# onion_dip_v1.net
KiCad netlist of a schematic drawn in EAGLE
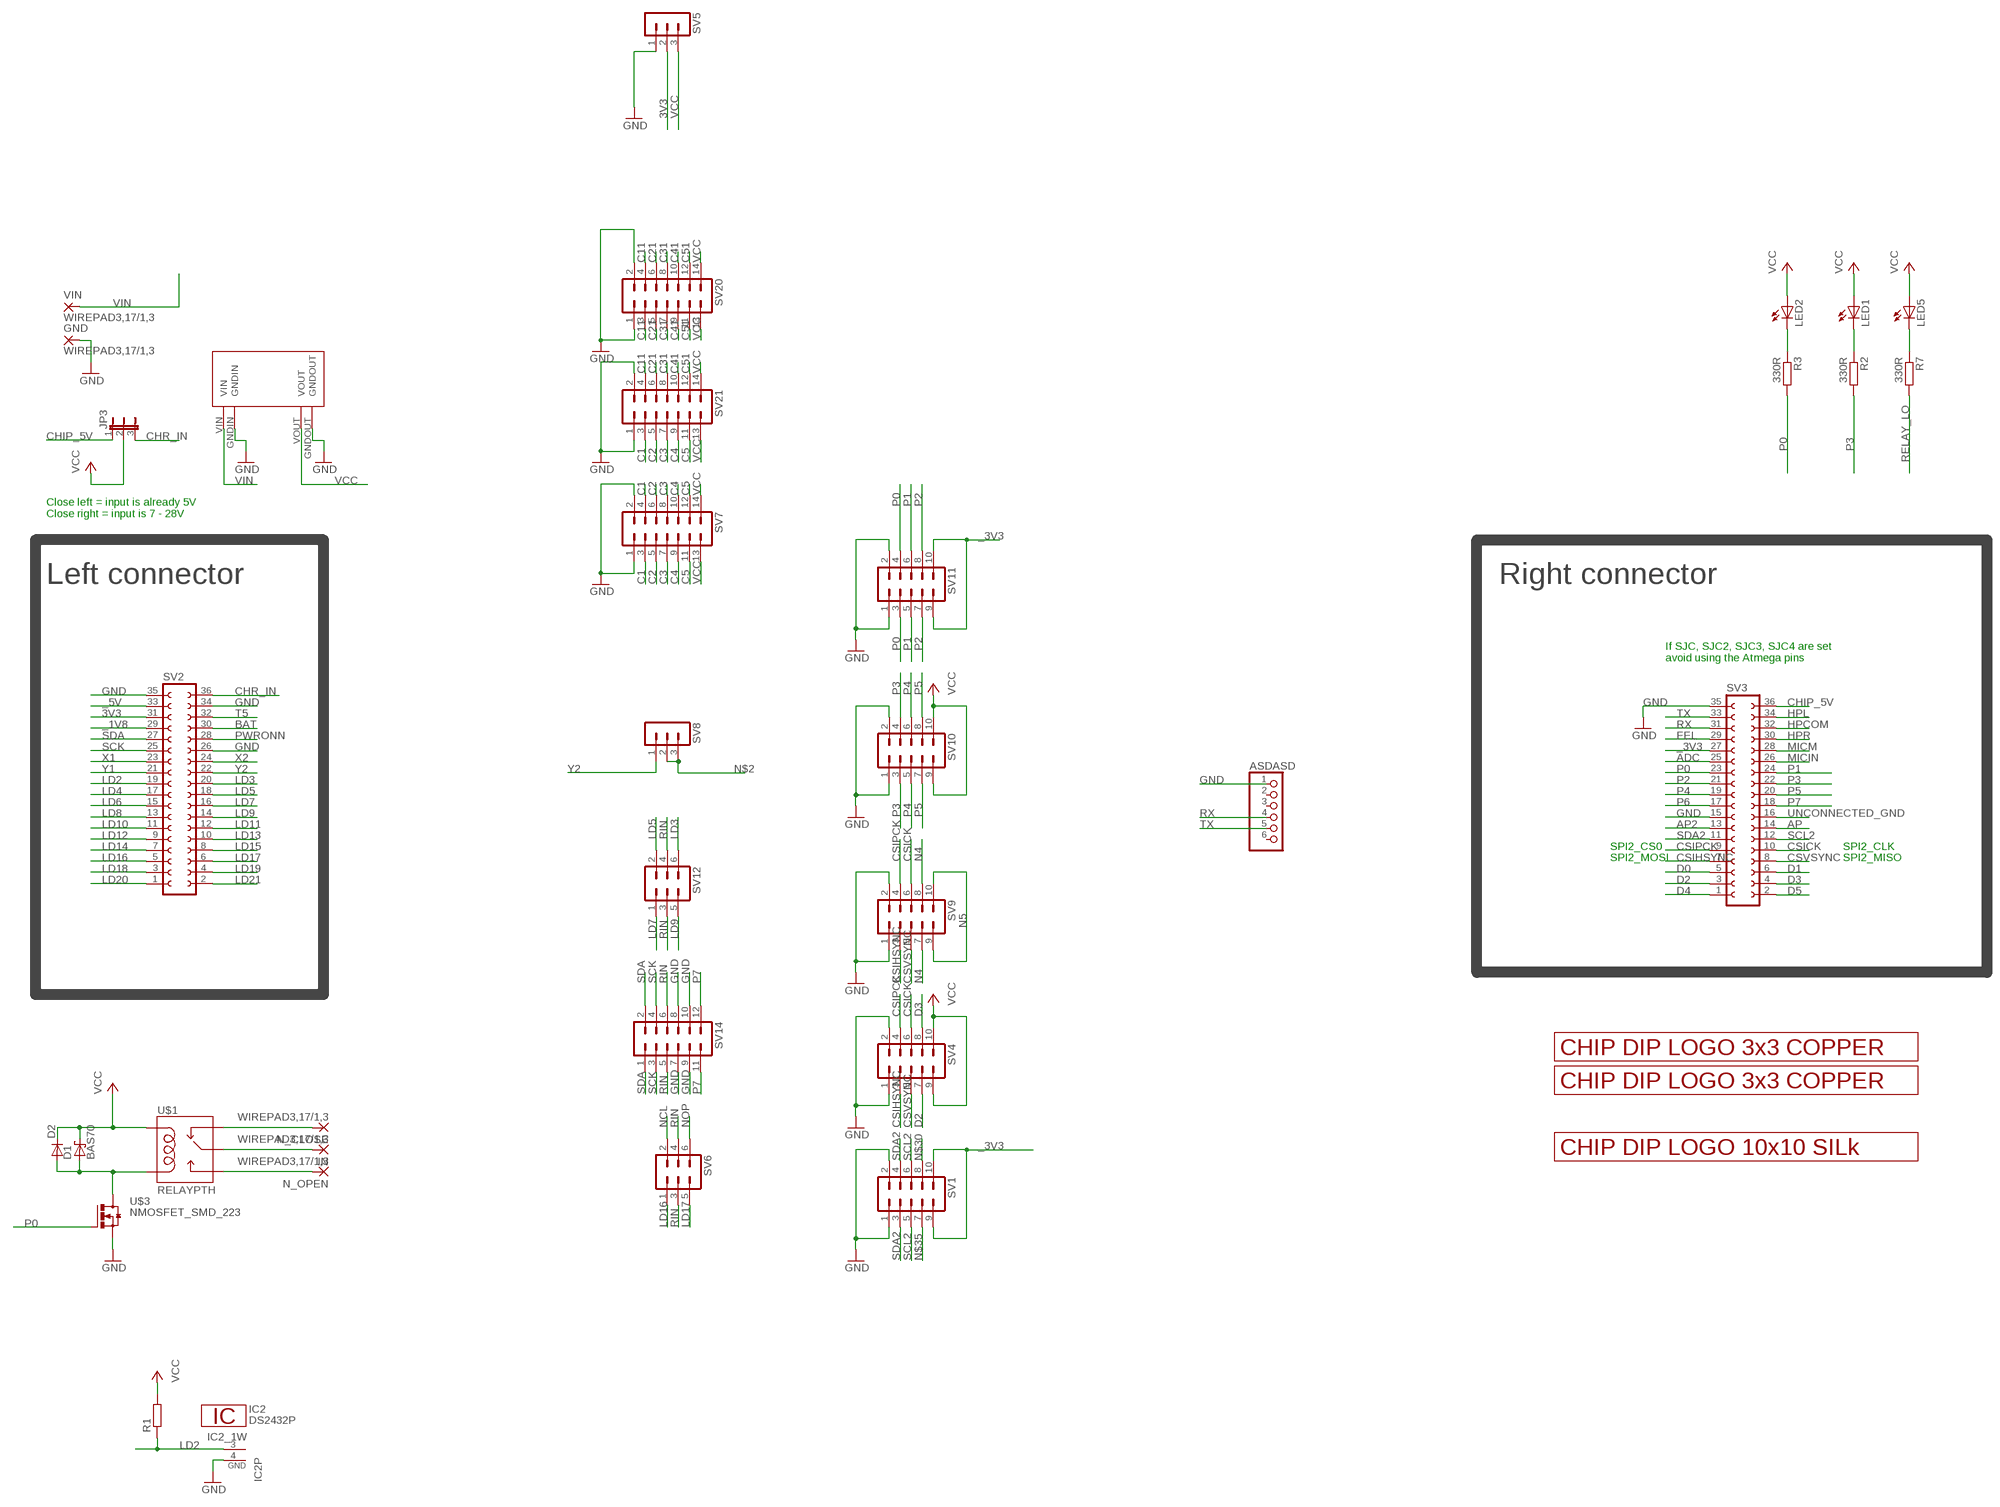
[diagram p0: schematic, sheet 1]

(export (version "E")
  (design (tool "Eeschema 10.0.6"))
  (components
    (comp (ref "ASDASD")
      (value "PINHD-1X6")
      (footprint "eagle-import:1X06")
      (libsource (lib "eagle-import") (part "PINHD-1X6"))
    )
    (comp (ref "D1")
      (value "BAS70")
      (footprint "eagle-import:SOT23")
      (libsource (lib "eagle-import") (part "BAS70"))
    )
    (comp (ref "D2")
      (value "DIODE-SMB")
      (footprint "eagle-import:SMB")
      (libsource (lib "eagle-import") (part "DIODE-SMB"))
    )
    (comp (ref "GND")
      (value "WIREPAD3,17/1,3")
      (footprint "eagle-import:3,17_1,3")
      (libsource (lib "eagle-import") (part "WIREPAD3,17/1,3"))
    )
    (comp (ref "IC2")
      (value "DS2432P")
      (footprint "eagle-import:TSOC6")
      (libsource (lib "eagle-import") (part "DS2432P"))
    )
    (comp (ref "IN")
      (value "WIREPAD3,17/1,3")
      (footprint "eagle-import:3,17_1,3")
      (libsource (lib "eagle-import") (part "WIREPAD3,17/1,3"))
    )
    (comp (ref "JP3")
      (value "JP2E")
      (footprint "eagle-import:JP2")
      (libsource (lib "eagle-import") (part "JP2E"))
    )
    (comp (ref "LED1")
      (value "LEDCHIP-LED0805")
      (footprint "eagle-import:CHIP-LED0805")
      (libsource (lib "eagle-import") (part "LEDCHIP-LED0805"))
    )
    (comp (ref "LED2")
      (value "LEDCHIP-LED0805")
      (footprint "eagle-import:CHIP-LED0805")
      (libsource (lib "eagle-import") (part "LEDCHIP-LED0805"))
    )
    (comp (ref "LED5")
      (value "LEDCHIP-LED0805")
      (footprint "eagle-import:CHIP-LED0805")
      (libsource (lib "eagle-import") (part "LEDCHIP-LED0805"))
    )
    (comp (ref "N_CLOSE")
      (value "WIREPAD3,17/1,3")
      (footprint "eagle-import:3,17_1,3")
      (libsource (lib "eagle-import") (part "WIREPAD3,17/1,3"))
    )
    (comp (ref "N_OPEN")
      (value "WIREPAD3,17/1,3")
      (footprint "eagle-import:3,17_1,3")
      (libsource (lib "eagle-import") (part "WIREPAD3,17/1,3"))
    )
    (comp (ref "R1")
      (value "R-EU_R0805")
      (footprint "eagle-import:R0805")
      (libsource (lib "eagle-import") (part "R-EU_R0805"))
    )
    (comp (ref "R2")
      (value "330R")
      (footprint "eagle-import:R0805")
      (libsource (lib "eagle-import") (part "R-EU_R0805"))
    )
    (comp (ref "R3")
      (value "330R")
      (footprint "eagle-import:R0805")
      (libsource (lib "eagle-import") (part "R-EU_R0805"))
    )
    (comp (ref "R7")
      (value "330R")
      (footprint "eagle-import:R0805")
      (libsource (lib "eagle-import") (part "R-EU_R0805"))
    )
    (comp (ref "SV1")
      (value "MA05-2")
      (footprint "eagle-import:MA05-2")
      (libsource (lib "eagle-import") (part "MA05-2"))
    )
    (comp (ref "SV2")
      (value "FE18-2")
      (footprint "eagle-import:FE18-2")
      (libsource (lib "eagle-import") (part "FE18-2"))
    )
    (comp (ref "SV3")
      (value "FE18-2")
      (footprint "eagle-import:FE18-2")
      (libsource (lib "eagle-import") (part "FE18-2"))
    )
    (comp (ref "SV4")
      (value "MA05-2")
      (footprint "eagle-import:MA05-2")
      (libsource (lib "eagle-import") (part "MA05-2"))
    )
    (comp (ref "SV5")
      (value "MA03-1")
      (footprint "eagle-import:MA03-1")
      (libsource (lib "eagle-import") (part "MA03-1"))
    )
    (comp (ref "SV6")
      (value "MA03-2")
      (footprint "eagle-import:MA03-2")
      (libsource (lib "eagle-import") (part "MA03-2"))
    )
    (comp (ref "SV7")
      (value "MA07-2")
      (footprint "eagle-import:MA07-2")
      (libsource (lib "eagle-import") (part "MA07-2"))
    )
    (comp (ref "SV8")
      (value "MA03-1")
      (footprint "eagle-import:MA03-1")
      (libsource (lib "eagle-import") (part "MA03-1"))
    )
    (comp (ref "SV9")
      (value "MA05-2")
      (footprint "eagle-import:MA05-2")
      (libsource (lib "eagle-import") (part "MA05-2"))
    )
    (comp (ref "SV10")
      (value "MA05-2")
      (footprint "eagle-import:MA05-2")
      (libsource (lib "eagle-import") (part "MA05-2"))
    )
    (comp (ref "SV11")
      (value "MA05-2")
      (footprint "eagle-import:MA05-2")
      (libsource (lib "eagle-import") (part "MA05-2"))
    )
    (comp (ref "SV12")
      (value "MA03-2")
      (footprint "eagle-import:MA03-2")
      (libsource (lib "eagle-import") (part "MA03-2"))
    )
    (comp (ref "SV14")
      (value "MA06-2")
      (footprint "eagle-import:MA06-2")
      (libsource (lib "eagle-import") (part "MA06-2"))
    )
    (comp (ref "SV20")
      (value "MA07-2")
      (footprint "eagle-import:MA07-2")
      (libsource (lib "eagle-import") (part "MA07-2"))
    )
    (comp (ref "SV21")
      (value "MA07-2")
      (footprint "eagle-import:MA07-2")
      (libsource (lib "eagle-import") (part "MA07-2"))
    )
    (comp (ref "U$1")
      (value "RELAYPTH")
      (footprint "eagle-import:SRD-05VDC-SL-C")
      (libsource (lib "eagle-import") (part "RELAYPTH"))
    )
    (comp (ref "U$3")
      (value "NMOSFET_SMD_223")
      (footprint "eagle-import:SOT223")
      (libsource (lib "eagle-import") (part "NMOSFET_SMD_223"))
    )
    (comp (ref "U$4")
      (value "LOGO_3X3_COPPER")
      (footprint "eagle-import:LOGO_3X3_COPPER")
      (libsource (lib "eagle-import") (part "LOGO_3X3_COPPER"))
    )
    (comp (ref "U$5")
      (value "LOGO_10X10_SILK")
      (footprint "eagle-import:LOGO_10X10_SILK")
      (libsource (lib "eagle-import") (part "LOGO_10X10_SILK"))
    )
    (comp (ref "U$6")
      (value "LOGO_3X3_COPPER")
      (footprint "eagle-import:LOGO_3X3_COPPER")
      (libsource (lib "eagle-import") (part "LOGO_3X3_COPPER"))
    )
    (comp (ref "U$9")
      (value "MP1584EN_FRAMELESS")
      (footprint "eagle-import:MP1584EN_FRAMELESS")
      (libsource (lib "eagle-import") (part "MP1584EN_FRAMELESS"))
    )
    (comp (ref "VIN")
      (value "WIREPAD3,17/1,3")
      (footprint "eagle-import:3,17_1,3")
      (libsource (lib "eagle-import") (part "WIREPAD3,17/1,3"))
    )
  )
  (nets
    (net (code "1") (name "/3V3") (class "Default")
      (node (ref "SV2") (pin "31") (pinfunction "31_31") (pintype "passive"))
      (node (ref "SV5") (pin "2") (pinfunction "2_2") (pintype "passive"))
    )
    (net (code "2") (name "/ADC") (class "Default")
      (node (ref "SV3") (pin "25") (pinfunction "25_25") (pintype "passive"))
    )
    (net (code "3") (name "/AP") (class "Default")
      (node (ref "SV3") (pin "14") (pinfunction "14_14") (pintype "passive"))
    )
    (net (code "4") (name "/AP2") (class "Default")
      (node (ref "SV3") (pin "13") (pinfunction "13_13") (pintype "passive"))
    )
    (net (code "5") (name "/BAT") (class "Default")
      (node (ref "SV2") (pin "30") (pinfunction "30_30") (pintype "passive"))
    )
    (net (code "6") (name "/C1") (class "Default")
      (node (ref "SV21") (pin "3") (pinfunction "3_3") (pintype "passive"))
      (node (ref "SV7") (pin "3") (pinfunction "3_3") (pintype "passive"))
      (node (ref "SV7") (pin "4") (pinfunction "4_4") (pintype "passive"))
    )
    (net (code "7") (name "/C2") (class "Default")
      (node (ref "SV21") (pin "5") (pinfunction "5_5") (pintype "passive"))
      (node (ref "SV7") (pin "5") (pinfunction "5_5") (pintype "passive"))
      (node (ref "SV7") (pin "6") (pinfunction "6_6") (pintype "passive"))
    )
    (net (code "8") (name "/C3") (class "Default")
      (node (ref "SV21") (pin "7") (pinfunction "7_7") (pintype "passive"))
      (node (ref "SV7") (pin "7") (pinfunction "7_7") (pintype "passive"))
      (node (ref "SV7") (pin "8") (pinfunction "8_8") (pintype "passive"))
    )
    (net (code "9") (name "/C4") (class "Default")
      (node (ref "SV21") (pin "9") (pinfunction "9_9") (pintype "passive"))
      (node (ref "SV7") (pin "10") (pinfunction "10_10") (pintype "passive"))
      (node (ref "SV7") (pin "9") (pinfunction "9_9") (pintype "passive"))
    )
    (net (code "10") (name "/C5") (class "Default")
      (node (ref "SV21") (pin "11") (pinfunction "11_11") (pintype "passive"))
      (node (ref "SV7") (pin "11") (pinfunction "11_11") (pintype "passive"))
      (node (ref "SV7") (pin "12") (pinfunction "12_12") (pintype "passive"))
    )
    (net (code "11") (name "/C11") (class "Default")
      (node (ref "SV20") (pin "3") (pinfunction "3_3") (pintype "passive"))
      (node (ref "SV20") (pin "4") (pinfunction "4_4") (pintype "passive"))
      (node (ref "SV21") (pin "4") (pinfunction "4_4") (pintype "passive"))
    )
    (net (code "12") (name "/C21") (class "Default")
      (node (ref "SV20") (pin "5") (pinfunction "5_5") (pintype "passive"))
      (node (ref "SV20") (pin "6") (pinfunction "6_6") (pintype "passive"))
      (node (ref "SV21") (pin "6") (pinfunction "6_6") (pintype "passive"))
    )
    (net (code "13") (name "/C31") (class "Default")
      (node (ref "SV20") (pin "7") (pinfunction "7_7") (pintype "passive"))
      (node (ref "SV20") (pin "8") (pinfunction "8_8") (pintype "passive"))
      (node (ref "SV21") (pin "8") (pinfunction "8_8") (pintype "passive"))
    )
    (net (code "14") (name "/C41") (class "Default")
      (node (ref "SV20") (pin "10") (pinfunction "10_10") (pintype "passive"))
      (node (ref "SV20") (pin "9") (pinfunction "9_9") (pintype "passive"))
      (node (ref "SV21") (pin "10") (pinfunction "10_10") (pintype "passive"))
    )
    (net (code "15") (name "/C51") (class "Default")
      (node (ref "SV20") (pin "11") (pinfunction "11_11") (pintype "passive"))
      (node (ref "SV20") (pin "12") (pinfunction "12_12") (pintype "passive"))
      (node (ref "SV21") (pin "12") (pinfunction "12_12") (pintype "passive"))
    )
    (net (code "16") (name "/CHIP_5V") (class "Default")
      (node (ref "JP3") (pin "1") (pinfunction "1_1") (pintype "passive"))
      (node (ref "SV3") (pin "36") (pinfunction "36_36") (pintype "passive"))
    )
    (net (code "17") (name "/CHR_IN") (class "Default")
      (node (ref "JP3") (pin "3") (pinfunction "3_3") (pintype "passive"))
      (node (ref "SV2") (pin "36") (pinfunction "36_36") (pintype "passive"))
    )
    (net (code "18") (name "/CSICK") (class "Default")
      (node (ref "SV3") (pin "10") (pinfunction "10_10") (pintype "passive"))
      (node (ref "SV4") (pin "6") (pinfunction "6_6") (pintype "passive"))
      (node (ref "SV9") (pin "6") (pinfunction "6_6") (pintype "passive"))
    )
    (net (code "19") (name "/CSIHSYNC") (class "Default")
      (node (ref "SV3") (pin "7") (pinfunction "7_7") (pintype "passive"))
      (node (ref "SV4") (pin "3") (pinfunction "3_3") (pintype "passive"))
      (node (ref "SV9") (pin "3") (pinfunction "3_3") (pintype "passive"))
    )
    (net (code "20") (name "/CSIPCK") (class "Default")
      (node (ref "SV3") (pin "9") (pinfunction "9_9") (pintype "passive"))
      (node (ref "SV4") (pin "4") (pinfunction "4_4") (pintype "passive"))
      (node (ref "SV9") (pin "4") (pinfunction "4_4") (pintype "passive"))
    )
    (net (code "21") (name "/CSVSYNC") (class "Default")
      (node (ref "SV3") (pin "8") (pinfunction "8_8") (pintype "passive"))
      (node (ref "SV4") (pin "5") (pinfunction "5_5") (pintype "passive"))
      (node (ref "SV9") (pin "5") (pinfunction "5_5") (pintype "passive"))
    )
    (net (code "22") (name "/D0") (class "Default")
      (node (ref "SV3") (pin "5") (pinfunction "5_5") (pintype "passive"))
    )
    (net (code "23") (name "/D1") (class "Default")
      (node (ref "SV3") (pin "6") (pinfunction "6_6") (pintype "passive"))
    )
    (net (code "24") (name "/D2") (class "Default")
      (node (ref "SV3") (pin "3") (pinfunction "3_3") (pintype "passive"))
      (node (ref "SV4") (pin "7") (pinfunction "7_7") (pintype "passive"))
    )
    (net (code "25") (name "/D3") (class "Default")
      (node (ref "SV3") (pin "4") (pinfunction "4_4") (pintype "passive"))
      (node (ref "SV4") (pin "8") (pinfunction "8_8") (pintype "passive"))
    )
    (net (code "26") (name "/D4") (class "Default")
      (node (ref "SV3") (pin "1") (pinfunction "1_1") (pintype "passive"))
    )
    (net (code "27") (name "/D5") (class "Default")
      (node (ref "SV3") (pin "2") (pinfunction "2_2") (pintype "passive"))
    )
    (net (code "28") (name "/FEL") (class "Default")
      (node (ref "SV3") (pin "29") (pinfunction "29_29") (pintype "passive"))
    )
    (net (code "29") (name "/HPCOM") (class "Default")
      (node (ref "SV3") (pin "32") (pinfunction "32_32") (pintype "passive"))
    )
    (net (code "30") (name "/HPL") (class "Default")
      (node (ref "SV3") (pin "34") (pinfunction "34_34") (pintype "passive"))
    )
    (net (code "31") (name "/HPR") (class "Default")
      (node (ref "SV3") (pin "30") (pinfunction "30_30") (pintype "passive"))
    )
    (net (code "32") (name "/LD2") (class "Default")
      (node (ref "IC2") (pin "3") (pinfunction "1W_3") (pintype "power_in"))
      (node (ref "R1") (pin "1") (pinfunction "1_1") (pintype "passive"))
      (node (ref "SV2") (pin "19") (pinfunction "19_19") (pintype "passive"))
    )
    (net (code "33") (name "/LD3") (class "Default")
      (node (ref "SV12") (pin "6") (pinfunction "6_6") (pintype "passive"))
      (node (ref "SV2") (pin "20") (pinfunction "20_20") (pintype "passive"))
    )
    (net (code "34") (name "/LD4") (class "Default")
      (node (ref "SV2") (pin "17") (pinfunction "17_17") (pintype "passive"))
    )
    (net (code "35") (name "/LD5") (class "Default")
      (node (ref "SV12") (pin "2") (pinfunction "2_2") (pintype "passive"))
      (node (ref "SV2") (pin "18") (pinfunction "18_18") (pintype "passive"))
    )
    (net (code "36") (name "/LD6") (class "Default")
      (node (ref "SV2") (pin "15") (pinfunction "15_15") (pintype "passive"))
    )
    (net (code "37") (name "/LD7") (class "Default")
      (node (ref "SV12") (pin "1") (pinfunction "1_1") (pintype "passive"))
      (node (ref "SV2") (pin "16") (pinfunction "16_16") (pintype "passive"))
    )
    (net (code "38") (name "/LD8") (class "Default")
      (node (ref "SV2") (pin "13") (pinfunction "13_13") (pintype "passive"))
    )
    (net (code "39") (name "/LD9") (class "Default")
      (node (ref "SV12") (pin "5") (pinfunction "5_5") (pintype "passive"))
      (node (ref "SV2") (pin "14") (pinfunction "14_14") (pintype "passive"))
    )
    (net (code "40") (name "/LD10") (class "Default")
      (node (ref "SV2") (pin "11") (pinfunction "11_11") (pintype "passive"))
    )
    (net (code "41") (name "/LD11") (class "Default")
      (node (ref "SV2") (pin "12") (pinfunction "12_12") (pintype "passive"))
    )
    (net (code "42") (name "/LD12") (class "Default")
      (node (ref "SV2") (pin "9") (pinfunction "9_9") (pintype "passive"))
    )
    (net (code "43") (name "/LD13") (class "Default")
      (node (ref "SV2") (pin "10") (pinfunction "10_10") (pintype "passive"))
    )
    (net (code "44") (name "/LD14") (class "Default")
      (node (ref "SV2") (pin "7") (pinfunction "7_7") (pintype "passive"))
    )
    (net (code "45") (name "/LD15") (class "Default")
      (node (ref "SV2") (pin "8") (pinfunction "8_8") (pintype "passive"))
    )
    (net (code "46") (name "/LD16") (class "Default")
      (node (ref "SV2") (pin "5") (pinfunction "5_5") (pintype "passive"))
      (node (ref "SV6") (pin "1") (pinfunction "1_1") (pintype "passive"))
    )
    (net (code "47") (name "/LD17") (class "Default")
      (node (ref "SV2") (pin "6") (pinfunction "6_6") (pintype "passive"))
      (node (ref "SV6") (pin "5") (pinfunction "5_5") (pintype "passive"))
    )
    (net (code "48") (name "/LD18") (class "Default")
      (node (ref "SV2") (pin "3") (pinfunction "3_3") (pintype "passive"))
    )
    (net (code "49") (name "/LD19") (class "Default")
      (node (ref "SV2") (pin "4") (pinfunction "4_4") (pintype "passive"))
    )
    (net (code "50") (name "/LD20") (class "Default")
      (node (ref "SV2") (pin "1") (pinfunction "1_1") (pintype "passive"))
    )
    (net (code "51") (name "/LD21") (class "Default")
      (node (ref "SV2") (pin "2") (pinfunction "2_2") (pintype "passive"))
    )
    (net (code "52") (name "/MICIN") (class "Default")
      (node (ref "SV3") (pin "26") (pinfunction "26_26") (pintype "passive"))
    )
    (net (code "53") (name "/MICM") (class "Default")
      (node (ref "SV3") (pin "28") (pinfunction "28_28") (pintype "passive"))
    )
    (net (code "54") (name "/N$2") (class "Default")
      (node (ref "SV8") (pin "2") (pinfunction "2_2") (pintype "passive"))
      (node (ref "SV8") (pin "3") (pinfunction "3_3") (pintype "passive"))
    )
    (net (code "55") (name "/N$30") (class "Default")
      (node (ref "SV1") (pin "8") (pinfunction "8_8") (pintype "passive"))
    )
    (net (code "56") (name "/N$35") (class "Default")
      (node (ref "SV1") (pin "7") (pinfunction "7_7") (pintype "passive"))
    )
    (net (code "57") (name "/N4") (class "Default")
      (node (ref "SV9") (pin "7") (pinfunction "7_7") (pintype "passive"))
      (node (ref "SV9") (pin "8") (pinfunction "8_8") (pintype "passive"))
    )
    (net (code "58") (name "/N5") (class "Default")
      (node (ref "SV9") (pin "10") (pinfunction "10_10") (pintype "passive"))
      (node (ref "SV9") (pin "9") (pinfunction "9_9") (pintype "passive"))
    )
    (net (code "59") (name "/NCL") (class "Default")
      (node (ref "N_CLOSE") (pin "1") (pinfunction "P_1") (pintype "passive"))
      (node (ref "SV6") (pin "2") (pinfunction "2_2") (pintype "passive"))
      (node (ref "U$1") (pin "SWCLOSED") (pinfunction "SWCLOSE_SWCLOSED") (pintype "bidirectional"))
    )
    (net (code "60") (name "/NOP") (class "Default")
      (node (ref "N_OPEN") (pin "1") (pinfunction "P_1") (pintype "passive"))
      (node (ref "SV6") (pin "6") (pinfunction "6_6") (pintype "passive"))
      (node (ref "U$1") (pin "SWOPEN") (pinfunction "SWOPEN_SWOPEN") (pintype "bidirectional"))
    )
    (net (code "61") (name "/P0") (class "Default")
      (node (ref "R3") (pin "2") (pinfunction "2_2") (pintype "passive"))
      (node (ref "SV11") (pin "3") (pinfunction "3_3") (pintype "passive"))
      (node (ref "SV11") (pin "4") (pinfunction "4_4") (pintype "passive"))
      (node (ref "SV3") (pin "23") (pinfunction "23_23") (pintype "passive"))
      (node (ref "U$3") (pin "1") (pinfunction "G_1") (pintype "passive"))
    )
    (net (code "62") (name "/P1") (class "Default")
      (node (ref "SV11") (pin "5") (pinfunction "5_5") (pintype "passive"))
      (node (ref "SV11") (pin "6") (pinfunction "6_6") (pintype "passive"))
      (node (ref "SV3") (pin "24") (pinfunction "24_24") (pintype "passive"))
    )
    (net (code "63") (name "/P2") (class "Default")
      (node (ref "SV11") (pin "7") (pinfunction "7_7") (pintype "passive"))
      (node (ref "SV11") (pin "8") (pinfunction "8_8") (pintype "passive"))
      (node (ref "SV3") (pin "21") (pinfunction "21_21") (pintype "passive"))
    )
    (net (code "64") (name "/P3") (class "Default")
      (node (ref "R2") (pin "2") (pinfunction "2_2") (pintype "passive"))
      (node (ref "SV10") (pin "3") (pinfunction "3_3") (pintype "passive"))
      (node (ref "SV10") (pin "4") (pinfunction "4_4") (pintype "passive"))
      (node (ref "SV3") (pin "22") (pinfunction "22_22") (pintype "passive"))
    )
    (net (code "65") (name "/P4") (class "Default")
      (node (ref "SV10") (pin "5") (pinfunction "5_5") (pintype "passive"))
      (node (ref "SV10") (pin "6") (pinfunction "6_6") (pintype "passive"))
      (node (ref "SV3") (pin "19") (pinfunction "19_19") (pintype "passive"))
    )
    (net (code "66") (name "/P5") (class "Default")
      (node (ref "SV10") (pin "7") (pinfunction "7_7") (pintype "passive"))
      (node (ref "SV10") (pin "8") (pinfunction "8_8") (pintype "passive"))
      (node (ref "SV3") (pin "20") (pinfunction "20_20") (pintype "passive"))
    )
    (net (code "67") (name "/P6") (class "Default")
      (node (ref "SV3") (pin "17") (pinfunction "17_17") (pintype "passive"))
    )
    (net (code "68") (name "/P7") (class "Default")
      (node (ref "SV14") (pin "11") (pinfunction "11_11") (pintype "passive"))
      (node (ref "SV14") (pin "12") (pinfunction "12_12") (pintype "passive"))
      (node (ref "SV3") (pin "18") (pinfunction "18_18") (pintype "passive"))
    )
    (net (code "69") (name "/PWRONN") (class "Default")
      (node (ref "SV2") (pin "28") (pinfunction "28_28") (pintype "passive"))
    )
    (net (code "70") (name "/RELAY_LO") (class "Default")
      (node (ref "D1") (pin "1") (pinfunction "A_1") (pintype "passive"))
      (node (ref "D2") (pin "A") (pinfunction "A_A") (pintype "passive"))
      (node (ref "R7") (pin "2") (pinfunction "2_2") (pintype "passive"))
      (node (ref "U$1") (pin "COIL0") (pinfunction "COIL0_COIL0") (pintype "bidirectional"))
      (node (ref "U$3") (pin "2") (pinfunction "D_2") (pintype "passive"))
      (node (ref "U$3") (pin "4") (pinfunction "D_4") (pintype "passive"))
    )
    (net (code "71") (name "/RIN") (class "Default")
      (node (ref "IN") (pin "1") (pinfunction "P_1") (pintype "passive"))
      (node (ref "SV12") (pin "3") (pinfunction "3_3") (pintype "passive"))
      (node (ref "SV12") (pin "4") (pinfunction "4_4") (pintype "passive"))
      (node (ref "SV14") (pin "5") (pinfunction "5_5") (pintype "passive"))
      (node (ref "SV14") (pin "6") (pinfunction "6_6") (pintype "passive"))
      (node (ref "SV6") (pin "3") (pinfunction "3_3") (pintype "passive"))
      (node (ref "SV6") (pin "4") (pinfunction "4_4") (pintype "passive"))
      (node (ref "U$1") (pin "SWCOMMON") (pinfunction "SWCOMMON_SWCOMMON") (pintype "bidirectional"))
    )
    (net (code "72") (name "/RX") (class "Default")
      (node (ref "ASDASD") (pin "4") (pinfunction "4_4") (pintype "passive"))
      (node (ref "SV3") (pin "31") (pinfunction "31_31") (pintype "passive"))
    )
    (net (code "73") (name "/SCK") (class "Default")
      (node (ref "SV14") (pin "3") (pinfunction "3_3") (pintype "passive"))
      (node (ref "SV14") (pin "4") (pinfunction "4_4") (pintype "passive"))
      (node (ref "SV2") (pin "25") (pinfunction "25_25") (pintype "passive"))
    )
    (net (code "74") (name "/SCL2") (class "Default")
      (node (ref "SV1") (pin "5") (pinfunction "5_5") (pintype "passive"))
      (node (ref "SV1") (pin "6") (pinfunction "6_6") (pintype "passive"))
      (node (ref "SV3") (pin "12") (pinfunction "12_12") (pintype "passive"))
    )
    (net (code "75") (name "/SDA") (class "Default")
      (node (ref "SV14") (pin "1") (pinfunction "1_1") (pintype "passive"))
      (node (ref "SV14") (pin "2") (pinfunction "2_2") (pintype "passive"))
      (node (ref "SV2") (pin "27") (pinfunction "27_27") (pintype "passive"))
    )
    (net (code "76") (name "/SDA2") (class "Default")
      (node (ref "SV1") (pin "3") (pinfunction "3_3") (pintype "passive"))
      (node (ref "SV1") (pin "4") (pinfunction "4_4") (pintype "passive"))
      (node (ref "SV3") (pin "11") (pinfunction "11_11") (pintype "passive"))
    )
    (net (code "77") (name "/T5") (class "Default")
      (node (ref "SV2") (pin "32") (pinfunction "32_32") (pintype "passive"))
    )
    (net (code "78") (name "/TX") (class "Default")
      (node (ref "ASDASD") (pin "5") (pinfunction "5_5") (pintype "passive"))
      (node (ref "SV3") (pin "33") (pinfunction "33_33") (pintype "passive"))
    )
    (net (code "79") (name "/UNCONNECTED_GND") (class "Default")
      (node (ref "SV3") (pin "16") (pinfunction "16_16") (pintype "passive"))
    )
    (net (code "80") (name "/VIN") (class "Default")
      (node (ref "U$9") (pin "VIN") (pinfunction "VIN_VIN") (pintype "power_in"))
      (node (ref "VIN") (pin "1") (pinfunction "P_1") (pintype "passive"))
    )
    (net (code "81") (name "/X1") (class "Default")
      (node (ref "SV2") (pin "23") (pinfunction "23_23") (pintype "passive"))
    )
    (net (code "82") (name "/X2") (class "Default")
      (node (ref "SV2") (pin "24") (pinfunction "24_24") (pintype "passive"))
    )
    (net (code "83") (name "/Y1") (class "Default")
      (node (ref "SV2") (pin "21") (pinfunction "21_21") (pintype "passive"))
    )
    (net (code "84") (name "/Y2") (class "Default")
      (node (ref "SV2") (pin "22") (pinfunction "22_22") (pintype "passive"))
      (node (ref "SV8") (pin "1") (pinfunction "1_1") (pintype "passive"))
    )
    (net (code "85") (name "/_1V8") (class "Default")
      (node (ref "SV2") (pin "29") (pinfunction "29_29") (pintype "passive"))
    )
    (net (code "86") (name "/_3V3") (class "Default")
      (node (ref "SV1") (pin "10") (pinfunction "10_10") (pintype "passive"))
      (node (ref "SV1") (pin "9") (pinfunction "9_9") (pintype "passive"))
      (node (ref "SV11") (pin "10") (pinfunction "10_10") (pintype "passive"))
      (node (ref "SV11") (pin "9") (pinfunction "9_9") (pintype "passive"))
      (node (ref "SV3") (pin "27") (pinfunction "27_27") (pintype "passive"))
    )
    (net (code "87") (name "/_5V") (class "Default")
      (node (ref "SV2") (pin "33") (pinfunction "33_33") (pintype "passive"))
    )
    (net (code "88") (name "GND") (class "Default")
      (node (ref "ASDASD") (pin "1") (pinfunction "1_1") (pintype "passive"))
      (node (ref "GND") (pin "1") (pinfunction "P_1") (pintype "passive"))
      (node (ref "IC2") (pin "4") (pinfunction "GND_4") (pintype "power_in"))
      (node (ref "SV1") (pin "1") (pinfunction "1_1") (pintype "passive"))
      (node (ref "SV1") (pin "2") (pinfunction "2_2") (pintype "passive"))
      (node (ref "SV10") (pin "1") (pinfunction "1_1") (pintype "passive"))
      (node (ref "SV10") (pin "2") (pinfunction "2_2") (pintype "passive"))
      (node (ref "SV11") (pin "1") (pinfunction "1_1") (pintype "passive"))
      (node (ref "SV11") (pin "2") (pinfunction "2_2") (pintype "passive"))
      (node (ref "SV14") (pin "10") (pinfunction "10_10") (pintype "passive"))
      (node (ref "SV14") (pin "7") (pinfunction "7_7") (pintype "passive"))
      (node (ref "SV14") (pin "8") (pinfunction "8_8") (pintype "passive"))
      (node (ref "SV14") (pin "9") (pinfunction "9_9") (pintype "passive"))
      (node (ref "SV2") (pin "26") (pinfunction "26_26") (pintype "passive"))
      (node (ref "SV2") (pin "34") (pinfunction "34_34") (pintype "passive"))
      (node (ref "SV2") (pin "35") (pinfunction "35_35") (pintype "passive"))
      (node (ref "SV20") (pin "1") (pinfunction "1_1") (pintype "passive"))
      (node (ref "SV20") (pin "2") (pinfunction "2_2") (pintype "passive"))
      (node (ref "SV21") (pin "1") (pinfunction "1_1") (pintype "passive"))
      (node (ref "SV21") (pin "2") (pinfunction "2_2") (pintype "passive"))
      (node (ref "SV3") (pin "15") (pinfunction "15_15") (pintype "passive"))
      (node (ref "SV3") (pin "35") (pinfunction "35_35") (pintype "passive"))
      (node (ref "SV4") (pin "1") (pinfunction "1_1") (pintype "passive"))
      (node (ref "SV4") (pin "2") (pinfunction "2_2") (pintype "passive"))
      (node (ref "SV5") (pin "1") (pinfunction "1_1") (pintype "passive"))
      (node (ref "SV7") (pin "1") (pinfunction "1_1") (pintype "passive"))
      (node (ref "SV7") (pin "2") (pinfunction "2_2") (pintype "passive"))
      (node (ref "SV9") (pin "1") (pinfunction "1_1") (pintype "passive"))
      (node (ref "SV9") (pin "2") (pinfunction "2_2") (pintype "passive"))
      (node (ref "U$3") (pin "3") (pinfunction "S_3") (pintype "passive"))
      (node (ref "U$9") (pin "GNDIN") (pinfunction "GNDIN_GNDIN") (pintype "power_in"))
      (node (ref "U$9") (pin "GNDOUT") (pinfunction "GNDOUT_GNDOUT") (pintype "power_in"))
    )
    (net (code "89") (name "Net-(LED1-PadC)") (class "Default")
      (node (ref "LED1") (pin "C") (pinfunction "C_C") (pintype "passive"))
      (node (ref "R2") (pin "1") (pinfunction "1_1") (pintype "passive"))
    )
    (net (code "90") (name "Net-(LED2-PadC)") (class "Default")
      (node (ref "LED2") (pin "C") (pinfunction "C_C") (pintype "passive"))
      (node (ref "R3") (pin "1") (pinfunction "1_1") (pintype "passive"))
    )
    (net (code "91") (name "Net-(LED5-PadC)") (class "Default")
      (node (ref "LED5") (pin "C") (pinfunction "C_C") (pintype "passive"))
      (node (ref "R7") (pin "1") (pinfunction "1_1") (pintype "passive"))
    )
    (net (code "92") (name "VCC") (class "Default")
      (node (ref "D1") (pin "3") (pinfunction "C_3") (pintype "passive"))
      (node (ref "D2") (pin "C") (pinfunction "C_C") (pintype "passive"))
      (node (ref "JP3") (pin "2") (pinfunction "2_2") (pintype "passive"))
      (node (ref "LED1") (pin "A") (pinfunction "A_A") (pintype "passive"))
      (node (ref "LED2") (pin "A") (pinfunction "A_A") (pintype "passive"))
      (node (ref "LED5") (pin "A") (pinfunction "A_A") (pintype "passive"))
      (node (ref "R1") (pin "2") (pinfunction "2_2") (pintype "passive"))
      (node (ref "SV10") (pin "10") (pinfunction "10_10") (pintype "passive"))
      (node (ref "SV10") (pin "9") (pinfunction "9_9") (pintype "passive"))
      (node (ref "SV20") (pin "13") (pinfunction "13_13") (pintype "passive"))
      (node (ref "SV20") (pin "14") (pinfunction "14_14") (pintype "passive"))
      (node (ref "SV21") (pin "13") (pinfunction "13_13") (pintype "passive"))
      (node (ref "SV21") (pin "14") (pinfunction "14_14") (pintype "passive"))
      (node (ref "SV4") (pin "10") (pinfunction "10_10") (pintype "passive"))
      (node (ref "SV4") (pin "9") (pinfunction "9_9") (pintype "passive"))
      (node (ref "SV5") (pin "3") (pinfunction "3_3") (pintype "passive"))
      (node (ref "SV7") (pin "13") (pinfunction "13_13") (pintype "passive"))
      (node (ref "SV7") (pin "14") (pinfunction "14_14") (pintype "passive"))
      (node (ref "U$1") (pin "COIL1") (pinfunction "COIL1_COIL1") (pintype "bidirectional"))
      (node (ref "U$9") (pin "VOUT") (pinfunction "VOUT_VOUT") (pintype "power_in"))
    )
    (net (code "93") (name "unconnected-(ASDASD-Pad2)") (class "Default")
      (node (ref "ASDASD") (pin "2") (pinfunction "2_2") (pintype "passive"))
    )
    (net (code "94") (name "unconnected-(ASDASD-Pad3)") (class "Default")
      (node (ref "ASDASD") (pin "3") (pinfunction "3_3") (pintype "passive"))
    )
    (net (code "95") (name "unconnected-(ASDASD-Pad6)") (class "Default")
      (node (ref "ASDASD") (pin "6") (pinfunction "6_6") (pintype "passive"))
    )
  )
)
